# SCHEM2.net
KiCad netlist of a schematic drawn in EAGLE
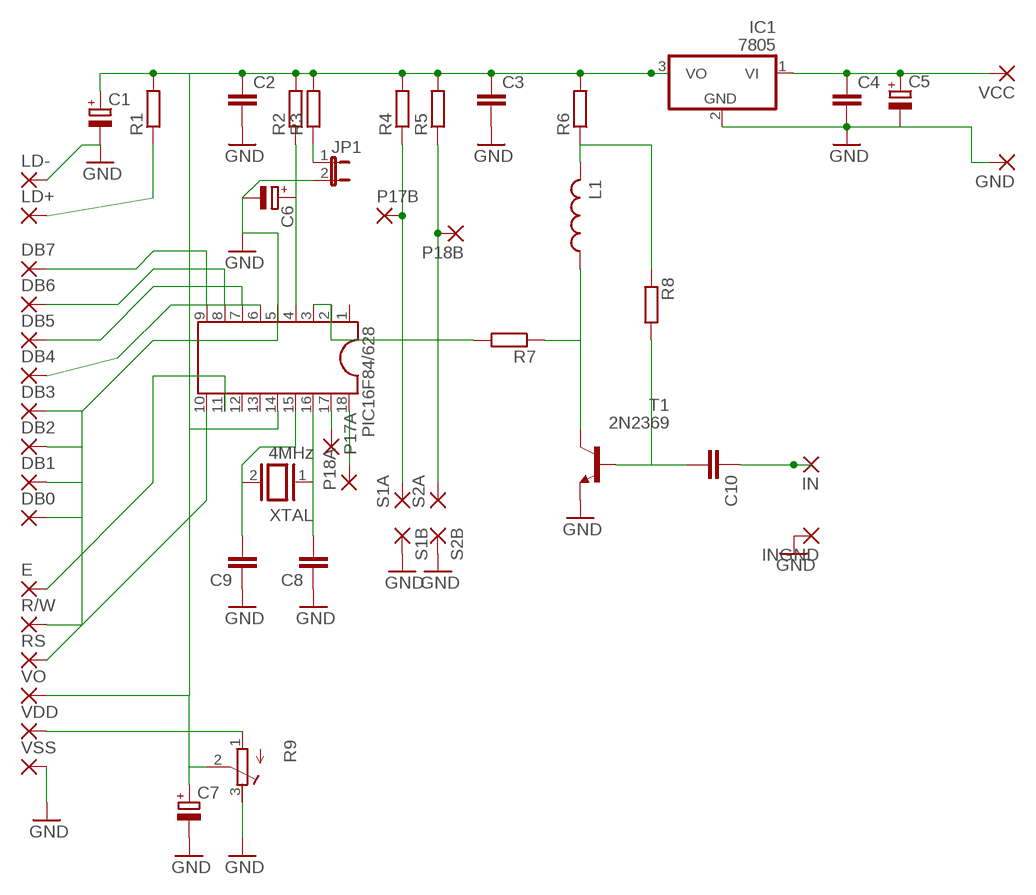
[diagram p0: schematic, sheet 1]

(export (version "E")
  (design (tool "Eeschema 10.0.6"))
  (components
    (comp (ref "C1")
      (value "CPOL-EUE3.5-8")
      (footprint "eagle-import:E3,5-8")
      (libsource (lib "eagle-import") (part "CPOL-EUE3.5-8"))
    )
    (comp (ref "C2")
      (value "C-EU025-040X050")
      (footprint "eagle-import:C025-040X050")
      (libsource (lib "eagle-import") (part "C-EU025-040X050"))
    )
    (comp (ref "C3")
      (value "C-EU025-040X050")
      (footprint "eagle-import:C025-040X050")
      (libsource (lib "eagle-import") (part "C-EU025-040X050"))
    )
    (comp (ref "C4")
      (value "C-EU025-040X050")
      (footprint "eagle-import:C025-040X050")
      (libsource (lib "eagle-import") (part "C-EU025-040X050"))
    )
    (comp (ref "C5")
      (value "CPOL-EUE3.5-8")
      (footprint "eagle-import:E3,5-8")
      (libsource (lib "eagle-import") (part "CPOL-EUE3.5-8"))
    )
    (comp (ref "C6")
      (value "CPOL-EUE3.5-8")
      (footprint "eagle-import:E3,5-8")
      (libsource (lib "eagle-import") (part "CPOL-EUE3.5-8"))
    )
    (comp (ref "C7")
      (value "CPOL-EUE3.5-8")
      (footprint "eagle-import:E3,5-8")
      (libsource (lib "eagle-import") (part "CPOL-EUE3.5-8"))
    )
    (comp (ref "C8")
      (value "C-EU025-040X050")
      (footprint "eagle-import:C025-040X050")
      (libsource (lib "eagle-import") (part "C-EU025-040X050"))
    )
    (comp (ref "C9")
      (value "C-EU025-040X050")
      (footprint "eagle-import:C025-040X050")
      (libsource (lib "eagle-import") (part "C-EU025-040X050"))
    )
    (comp (ref "C10")
      (value "C-EU025-040X050")
      (footprint "eagle-import:C025-040X050")
      (libsource (lib "eagle-import") (part "C-EU025-040X050"))
    )
    (comp (ref "DB0")
      (value "WIREPAD1,6/0,8")
      (footprint "eagle-import:1,6_0,8")
      (libsource (lib "eagle-import") (part "WIREPAD1,6/0,8"))
    )
    (comp (ref "DB1")
      (value "WIREPAD1,6/0,8")
      (footprint "eagle-import:1,6_0,8")
      (libsource (lib "eagle-import") (part "WIREPAD1,6/0,8"))
    )
    (comp (ref "DB2")
      (value "WIREPAD1,6/0,8")
      (footprint "eagle-import:1,6_0,8")
      (libsource (lib "eagle-import") (part "WIREPAD1,6/0,8"))
    )
    (comp (ref "DB3")
      (value "WIREPAD1,6/0,8")
      (footprint "eagle-import:1,6_0,8")
      (libsource (lib "eagle-import") (part "WIREPAD1,6/0,8"))
    )
    (comp (ref "DB4")
      (value "WIREPAD1,6/0,8")
      (footprint "eagle-import:1,6_0,8")
      (libsource (lib "eagle-import") (part "WIREPAD1,6/0,8"))
    )
    (comp (ref "DB5")
      (value "WIREPAD1,6/0,8")
      (footprint "eagle-import:1,6_0,8")
      (libsource (lib "eagle-import") (part "WIREPAD1,6/0,8"))
    )
    (comp (ref "DB6")
      (value "WIREPAD1,6/0,8")
      (footprint "eagle-import:1,6_0,8")
      (libsource (lib "eagle-import") (part "WIREPAD1,6/0,8"))
    )
    (comp (ref "DB7")
      (value "WIREPAD1,6/0,8")
      (footprint "eagle-import:1,6_0,8")
      (libsource (lib "eagle-import") (part "WIREPAD1,6/0,8"))
    )
    (comp (ref "E")
      (value "WIREPAD1,6/0,8")
      (footprint "eagle-import:1,6_0,8")
      (libsource (lib "eagle-import") (part "WIREPAD1,6/0,8"))
    )
    (comp (ref "GND")
      (value "WIREPAD1,6/0,8")
      (footprint "eagle-import:1,6_0,8")
      (libsource (lib "eagle-import") (part "WIREPAD1,6/0,8"))
    )
    (comp (ref "IC1")
      (value "7805")
      (footprint "eagle-import:TO220V")
      (libsource (lib "eagle-import") (part "78TV8"))
    )
    (comp (ref "IN")
      (value "WIREPAD1,6/0,8")
      (footprint "eagle-import:1,6_0,8")
      (libsource (lib "eagle-import") (part "WIREPAD1,6/0,8"))
    )
    (comp (ref "INGND")
      (value "WIREPAD1,6/0,8")
      (footprint "eagle-import:1,6_0,8")
      (libsource (lib "eagle-import") (part "WIREPAD1,6/0,8"))
    )
    (comp (ref "JP1")
      (value "JP1E")
      (footprint "eagle-import:JP1")
      (libsource (lib "eagle-import") (part "JP1E"))
    )
    (comp (ref "L1")
      (value "L-US0204/7")
      (footprint "eagle-import:0204_7")
      (libsource (lib "eagle-import") (part "L-US0204/7"))
    )
    (comp (ref "LD+")
      (value "WIREPAD1,6/0,8")
      (footprint "eagle-import:1,6_0,8")
      (libsource (lib "eagle-import") (part "WIREPAD1,6/0,8"))
    )
    (comp (ref "LD-")
      (value "WIREPAD1,6/0,8")
      (footprint "eagle-import:1,6_0,8")
      (libsource (lib "eagle-import") (part "WIREPAD1,6/0,8"))
    )
    (comp (ref "P17A")
      (value "WIREPAD1,6/0,8")
      (footprint "eagle-import:1,6_0,8")
      (libsource (lib "eagle-import") (part "WIREPAD1,6/0,8"))
    )
    (comp (ref "P17B")
      (value "WIREPAD1,6/0,8")
      (footprint "eagle-import:1,6_0,8")
      (libsource (lib "eagle-import") (part "WIREPAD1,6/0,8"))
    )
    (comp (ref "P18A")
      (value "WIREPAD1,6/0,8")
      (footprint "eagle-import:1,6_0,8")
      (libsource (lib "eagle-import") (part "WIREPAD1,6/0,8"))
    )
    (comp (ref "P18B")
      (value "WIREPAD1,6/0,8")
      (footprint "eagle-import:1,6_0,8")
      (libsource (lib "eagle-import") (part "WIREPAD1,6/0,8"))
    )
    (comp (ref "PIC16F84/628")
      (value "DIL18")
      (footprint "eagle-import:DIL18")
      (libsource (lib "eagle-import") (part "DIL18"))
    )
    (comp (ref "R/W")
      (value "WIREPAD1,6/0,8")
      (footprint "eagle-import:1,6_0,8")
      (libsource (lib "eagle-import") (part "WIREPAD1,6/0,8"))
    )
    (comp (ref "R1")
      (value "R-EU_0204/5")
      (footprint "eagle-import:0204_5")
      (libsource (lib "eagle-import") (part "R-EU_0204/5"))
    )
    (comp (ref "R2")
      (value "R-EU_0204/5")
      (footprint "eagle-import:0204_5")
      (libsource (lib "eagle-import") (part "R-EU_0204/5"))
    )
    (comp (ref "R3")
      (value "R-EU_0204/5")
      (footprint "eagle-import:0204_5")
      (libsource (lib "eagle-import") (part "R-EU_0204/5"))
    )
    (comp (ref "R4")
      (value "R-EU_0204/5")
      (footprint "eagle-import:0204_5")
      (libsource (lib "eagle-import") (part "R-EU_0204/5"))
    )
    (comp (ref "R5")
      (value "R-EU_0204/5")
      (footprint "eagle-import:0204_5")
      (libsource (lib "eagle-import") (part "R-EU_0204/5"))
    )
    (comp (ref "R6")
      (value "R-EU_0204/5")
      (footprint "eagle-import:0204_5")
      (libsource (lib "eagle-import") (part "R-EU_0204/5"))
    )
    (comp (ref "R7")
      (value "R-EU_0204/5")
      (footprint "eagle-import:0204_5")
      (libsource (lib "eagle-import") (part "R-EU_0204/5"))
    )
    (comp (ref "R8")
      (value "R-EU_0204/5")
      (footprint "eagle-import:0204_5")
      (libsource (lib "eagle-import") (part "R-EU_0204/5"))
    )
    (comp (ref "R9")
      (value "R-TRIMM3339P")
      (footprint "eagle-import:RTRIM3339P")
      (libsource (lib "eagle-import") (part "R-TRIMM3339P"))
    )
    (comp (ref "RS")
      (value "WIREPAD1,6/0,8")
      (footprint "eagle-import:1,6_0,8")
      (libsource (lib "eagle-import") (part "WIREPAD1,6/0,8"))
    )
    (comp (ref "S1A")
      (value "WIREPAD1,6/0,8")
      (footprint "eagle-import:1,6_0,8")
      (libsource (lib "eagle-import") (part "WIREPAD1,6/0,8"))
    )
    (comp (ref "S1B")
      (value "WIREPAD1,6/0,8")
      (footprint "eagle-import:1,6_0,8")
      (libsource (lib "eagle-import") (part "WIREPAD1,6/0,8"))
    )
    (comp (ref "S2A")
      (value "WIREPAD1,6/0,8")
      (footprint "eagle-import:1,6_0,8")
      (libsource (lib "eagle-import") (part "WIREPAD1,6/0,8"))
    )
    (comp (ref "S2B")
      (value "WIREPAD1,6/0,8")
      (footprint "eagle-import:1,6_0,8")
      (libsource (lib "eagle-import") (part "WIREPAD1,6/0,8"))
    )
    (comp (ref "T1")
      (value "2N2369")
      (footprint "eagle-import:TO18")
      (libsource (lib "eagle-import") (part "2N2369"))
    )
    (comp (ref "VCC")
      (value "WIREPAD1,6/0,8")
      (footprint "eagle-import:1,6_0,8")
      (libsource (lib "eagle-import") (part "WIREPAD1,6/0,8"))
    )
    (comp (ref "VDD")
      (value "WIREPAD1,6/0,8")
      (footprint "eagle-import:1,6_0,8")
      (libsource (lib "eagle-import") (part "WIREPAD1,6/0,8"))
    )
    (comp (ref "VO")
      (value "WIREPAD1,6/0,8")
      (footprint "eagle-import:1,6_0,8")
      (libsource (lib "eagle-import") (part "WIREPAD1,6/0,8"))
    )
    (comp (ref "VSS")
      (value "WIREPAD1,6/0,8")
      (footprint "eagle-import:1,6_0,8")
      (libsource (lib "eagle-import") (part "WIREPAD1,6/0,8"))
    )
    (comp (ref "XTAL")
      (value "4MHz")
      (footprint "eagle-import:QS")
      (libsource (lib "eagle-import") (part "XTAL/S"))
    )
  )
  (nets
    (net (code "1") (name "GND") (class "Default")
      (node (ref "C1") (pin "-") (pinfunction "-_-") (pintype "passive"))
      (node (ref "C2") (pin "2") (pinfunction "2_2") (pintype "passive"))
      (node (ref "C3") (pin "2") (pinfunction "2_2") (pintype "passive"))
      (node (ref "C4") (pin "2") (pinfunction "2_2") (pintype "passive"))
      (node (ref "C5") (pin "-") (pinfunction "-_-") (pintype "passive"))
      (node (ref "C6") (pin "-") (pinfunction "-_-") (pintype "passive"))
      (node (ref "C7") (pin "-") (pinfunction "-_-") (pintype "passive"))
      (node (ref "C8") (pin "1") (pinfunction "1_1") (pintype "passive"))
      (node (ref "C9") (pin "1") (pinfunction "1_1") (pintype "passive"))
      (node (ref "DB0") (pin "1") (pinfunction "P_1") (pintype "passive"))
      (node (ref "DB1") (pin "1") (pinfunction "P_1") (pintype "passive"))
      (node (ref "DB2") (pin "1") (pinfunction "P_1") (pintype "passive"))
      (node (ref "DB3") (pin "1") (pinfunction "P_1") (pintype "passive"))
      (node (ref "GND") (pin "1") (pinfunction "P_1") (pintype "passive"))
      (node (ref "IC1") (pin "2") (pinfunction "GND_2") (pintype "passive"))
      (node (ref "INGND") (pin "1") (pinfunction "P_1") (pintype "passive"))
      (node (ref "JP1") (pin "2") (pinfunction "2_2") (pintype "passive"))
      (node (ref "LD-") (pin "1") (pinfunction "P_1") (pintype "passive"))
      (node (ref "PIC16F84/628") (pin "5") (pinfunction "5_5") (pintype "passive"))
      (node (ref "R/W") (pin "1") (pinfunction "P_1") (pintype "passive"))
      (node (ref "R9") (pin "3") (pinfunction "E_3") (pintype "passive"))
      (node (ref "S1B") (pin "1") (pinfunction "P_1") (pintype "passive"))
      (node (ref "S2B") (pin "1") (pinfunction "P_1") (pintype "passive"))
      (node (ref "T1") (pin "1") (pinfunction "E_1") (pintype "passive"))
      (node (ref "VSS") (pin "1") (pinfunction "P_1") (pintype "passive"))
    )
    (net (code "2") (name "Net-(C6-Pad+)") (class "Default")
      (node (ref "C6") (pin "+") (pinfunction "+_+") (pintype "passive"))
      (node (ref "PIC16F84/628") (pin "4") (pinfunction "4_4") (pintype "passive"))
      (node (ref "R2") (pin "1") (pinfunction "1_1") (pintype "passive"))
    )
    (net (code "3") (name "Net-(C8-Pad2)") (class "Default")
      (node (ref "C8") (pin "2") (pinfunction "2_2") (pintype "passive"))
      (node (ref "PIC16F84/628") (pin "16") (pinfunction "16_16") (pintype "passive"))
      (node (ref "XTAL") (pin "1") (pinfunction "1_1") (pintype "passive"))
    )
    (net (code "4") (name "Net-(C9-Pad2)") (class "Default")
      (node (ref "C9") (pin "2") (pinfunction "2_2") (pintype "passive"))
      (node (ref "PIC16F84/628") (pin "15") (pinfunction "15_15") (pintype "passive"))
      (node (ref "XTAL") (pin "2") (pinfunction "2_2") (pintype "passive"))
    )
    (net (code "5") (name "Net-(DB4-P)") (class "Default")
      (node (ref "DB4") (pin "1") (pinfunction "P_1") (pintype "passive"))
      (node (ref "PIC16F84/628") (pin "6") (pinfunction "6_6") (pintype "passive"))
    )
    (net (code "6") (name "Net-(DB5-P)") (class "Default")
      (node (ref "DB5") (pin "1") (pinfunction "P_1") (pintype "passive"))
      (node (ref "PIC16F84/628") (pin "7") (pinfunction "7_7") (pintype "passive"))
    )
    (net (code "7") (name "Net-(DB6-P)") (class "Default")
      (node (ref "DB6") (pin "1") (pinfunction "P_1") (pintype "passive"))
      (node (ref "PIC16F84/628") (pin "8") (pinfunction "8_8") (pintype "passive"))
    )
    (net (code "8") (name "Net-(DB7-P)") (class "Default")
      (node (ref "DB7") (pin "1") (pinfunction "P_1") (pintype "passive"))
      (node (ref "PIC16F84/628") (pin "9") (pinfunction "9_9") (pintype "passive"))
    )
    (net (code "9") (name "Net-(E-P)") (class "Default")
      (node (ref "E") (pin "1") (pinfunction "P_1") (pintype "passive"))
      (node (ref "PIC16F84/628") (pin "11") (pinfunction "11_11") (pintype "passive"))
    )
    (net (code "10") (name "Net-(IC1-VI)") (class "Default")
      (node (ref "C4") (pin "1") (pinfunction "1_1") (pintype "passive"))
      (node (ref "C5") (pin "+") (pinfunction "+_+") (pintype "passive"))
      (node (ref "IC1") (pin "1") (pinfunction "VI_1") (pintype "input"))
      (node (ref "VCC") (pin "1") (pinfunction "P_1") (pintype "passive"))
    )
    (net (code "11") (name "Net-(IC1-VO)") (class "Default")
      (node (ref "C1") (pin "+") (pinfunction "+_+") (pintype "passive"))
      (node (ref "C2") (pin "1") (pinfunction "1_1") (pintype "passive"))
      (node (ref "C3") (pin "1") (pinfunction "1_1") (pintype "passive"))
      (node (ref "C7") (pin "+") (pinfunction "+_+") (pintype "passive"))
      (node (ref "IC1") (pin "3") (pinfunction "VO_3") (pintype "passive"))
      (node (ref "PIC16F84/628") (pin "14") (pinfunction "14_14") (pintype "passive"))
      (node (ref "R1") (pin "2") (pinfunction "2_2") (pintype "passive"))
      (node (ref "R2") (pin "2") (pinfunction "2_2") (pintype "passive"))
      (node (ref "R3") (pin "2") (pinfunction "2_2") (pintype "passive"))
      (node (ref "R4") (pin "2") (pinfunction "2_2") (pintype "passive"))
      (node (ref "R5") (pin "2") (pinfunction "2_2") (pintype "passive"))
      (node (ref "R6") (pin "2") (pinfunction "2_2") (pintype "passive"))
      (node (ref "R9") (pin "2") (pinfunction "S_2") (pintype "passive"))
      (node (ref "VO") (pin "1") (pinfunction "P_1") (pintype "passive"))
    )
    (net (code "12") (name "Net-(IN-P)") (class "Default")
      (node (ref "C10") (pin "1") (pinfunction "1_1") (pintype "passive"))
      (node (ref "IN") (pin "1") (pinfunction "P_1") (pintype "passive"))
    )
    (net (code "13") (name "Net-(JP1-Pad1)") (class "Default")
      (node (ref "JP1") (pin "1") (pinfunction "1_1") (pintype "passive"))
      (node (ref "R3") (pin "1") (pinfunction "1_1") (pintype "passive"))
    )
    (net (code "14") (name "Net-(L1-Pad2)") (class "Default")
      (node (ref "L1") (pin "2") (pinfunction "2_2") (pintype "passive"))
      (node (ref "R6") (pin "1") (pinfunction "1_1") (pintype "passive"))
      (node (ref "R8") (pin "1") (pinfunction "1_1") (pintype "passive"))
    )
    (net (code "15") (name "Net-(LD+-P)") (class "Default")
      (node (ref "LD+") (pin "1") (pinfunction "P_1") (pintype "passive"))
      (node (ref "R1") (pin "1") (pinfunction "1_1") (pintype "passive"))
    )
    (net (code "16") (name "Net-(P17A-P)") (class "Default")
      (node (ref "P17A") (pin "1") (pinfunction "P_1") (pintype "passive"))
      (node (ref "PIC16F84/628") (pin "17") (pinfunction "17_17") (pintype "passive"))
    )
    (net (code "17") (name "Net-(P17B-P)") (class "Default")
      (node (ref "P17B") (pin "1") (pinfunction "P_1") (pintype "passive"))
      (node (ref "R4") (pin "1") (pinfunction "1_1") (pintype "passive"))
      (node (ref "S1A") (pin "1") (pinfunction "P_1") (pintype "passive"))
    )
    (net (code "18") (name "Net-(P18A-P)") (class "Default")
      (node (ref "P18A") (pin "1") (pinfunction "P_1") (pintype "passive"))
      (node (ref "PIC16F84/628") (pin "18") (pinfunction "18_18") (pintype "passive"))
    )
    (net (code "19") (name "Net-(P18B-P)") (class "Default")
      (node (ref "P18B") (pin "1") (pinfunction "P_1") (pintype "passive"))
      (node (ref "R5") (pin "1") (pinfunction "1_1") (pintype "passive"))
      (node (ref "S2A") (pin "1") (pinfunction "P_1") (pintype "passive"))
    )
    (net (code "20") (name "Net-(PIC16F84/628-Pad2)") (class "Default")
      (node (ref "PIC16F84/628") (pin "2") (pinfunction "2_2") (pintype "passive"))
      (node (ref "PIC16F84/628") (pin "3") (pinfunction "3_3") (pintype "passive"))
      (node (ref "R7") (pin "2") (pinfunction "2_2") (pintype "passive"))
    )
    (net (code "21") (name "Net-(R9-A)") (class "Default")
      (node (ref "R9") (pin "1") (pinfunction "A_1") (pintype "passive"))
      (node (ref "VDD") (pin "1") (pinfunction "P_1") (pintype "passive"))
    )
    (net (code "22") (name "Net-(RS-P)") (class "Default")
      (node (ref "PIC16F84/628") (pin "10") (pinfunction "10_10") (pintype "passive"))
      (node (ref "RS") (pin "1") (pinfunction "P_1") (pintype "passive"))
    )
    (net (code "23") (name "Net-(T1-B)") (class "Default")
      (node (ref "C10") (pin "2") (pinfunction "2_2") (pintype "passive"))
      (node (ref "R8") (pin "2") (pinfunction "2_2") (pintype "passive"))
      (node (ref "T1") (pin "2") (pinfunction "B_2") (pintype "passive"))
    )
    (net (code "24") (name "Net-(T1-C)") (class "Default")
      (node (ref "L1") (pin "1") (pinfunction "1_1") (pintype "passive"))
      (node (ref "R7") (pin "1") (pinfunction "1_1") (pintype "passive"))
      (node (ref "T1") (pin "3") (pinfunction "C_3") (pintype "passive"))
    )
    (net (code "25") (name "unconnected-(PIC16F84/628-Pad1)") (class "Default")
      (node (ref "PIC16F84/628") (pin "1") (pinfunction "1_1") (pintype "passive"))
    )
    (net (code "26") (name "unconnected-(PIC16F84/628-Pad12)") (class "Default")
      (node (ref "PIC16F84/628") (pin "12") (pinfunction "12_12") (pintype "passive"))
    )
    (net (code "27") (name "unconnected-(PIC16F84/628-Pad13)") (class "Default")
      (node (ref "PIC16F84/628") (pin "13") (pinfunction "13_13") (pintype "passive"))
    )
  )
)
